# FB_Control.net
KiCad netlist of a schematic drawn in Altium Designer
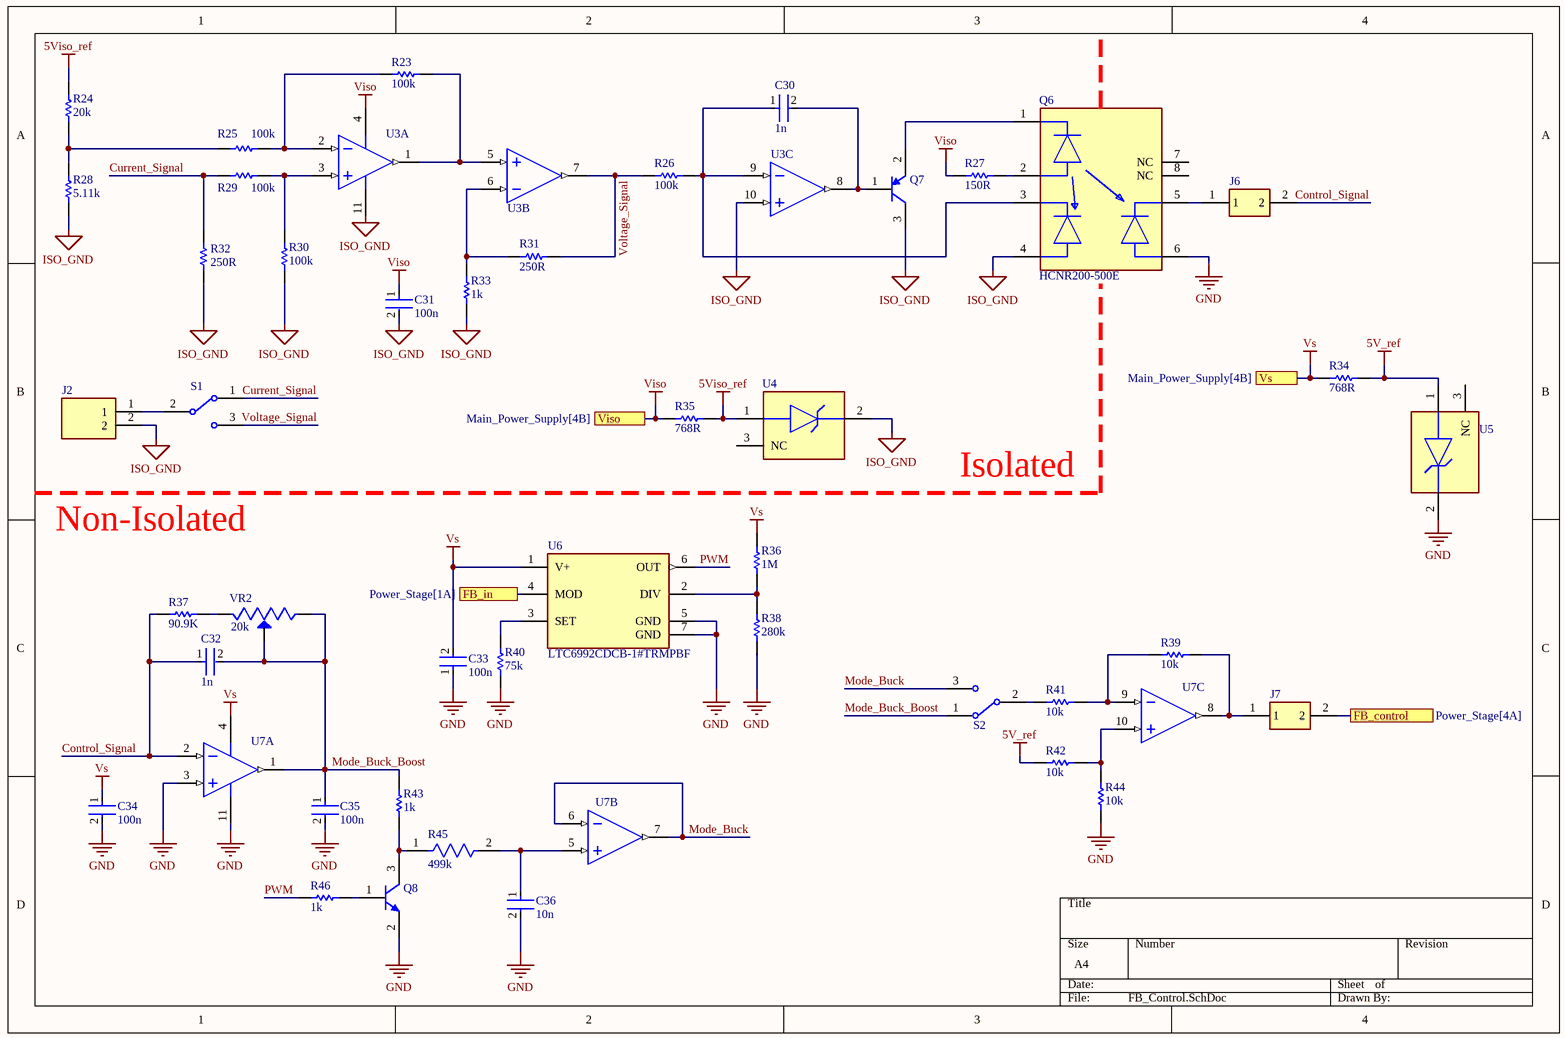
[diagram p0: FB_Control.SchDoc]

(export (version "E")
  (design (tool "Eeschema 10.0.6"))
  (components
    (comp (ref "C30")
      (value "1n")
      (footprint "FP-1206-L_3_2_0_2-W_1_6_0-IPC_C")
      (description "General Purpose Ceramic Capacitor, 1206, 1nF, 5%, NP0, 30ppm/°C, 100V")
      (fields (field (name "VOLTAGE") "100V") (field (name "TOLERANCE") "5%"))
      (libsource (lib "Altium Content Vault") (part "02cd4be3c70576c341d710602a673aa"))
    )
    (comp (ref "C31")
      (value "100n")
      (footprint "FP-0805-L_2_01_0_2-W_1_25-MFG")
      (description "General Purpose Ceramic Capacitor, 0805, 100nF, 5%, X7R, 0.15, 50V")
      (fields (field (name "TOLERANCE") "5%") (field (name "VOLTAGE") "50V"))
      (libsource (lib "Altium Content Vault") (part "02cd4be3c70576c341d710602a673aa"))
    )
    (comp (ref "C32")
      (value "1n")
      (footprint "FP-1206-L_3_2_0_2-W_1_6_0-IPC_C")
      (description "General Purpose Ceramic Capacitor, 1206, 1nF, 5%, NP0, 30ppm/°C, 100V")
      (fields (field (name "VOLTAGE") "100V") (field (name "TOLERANCE") "5%"))
      (libsource (lib "Altium Content Vault") (part "02cd4be3c70576c341d710602a673aa"))
    )
    (comp (ref "C33")
      (value "100n")
      (footprint "FP-0805-L_2_01_0_2-W_1_25-MFG")
      (description "General Purpose Ceramic Capacitor, 0805, 100nF, 5%, X7R, 0.15, 50V")
      (fields (field (name "TOLERANCE") "5%") (field (name "VOLTAGE") "50V"))
      (libsource (lib "Altium Content Vault") (part "02cd4be3c70576c341d710602a673aa"))
    )
    (comp (ref "C34")
      (value "100n")
      (footprint "FP-0805-L_2_01_0_2-W_1_25-MFG")
      (description "General Purpose Ceramic Capacitor, 0805, 100nF, 5%, X7R, 0.15, 50V")
      (fields (field (name "TOLERANCE") "5%") (field (name "VOLTAGE") "50V"))
      (libsource (lib "Altium Content Vault") (part "02cd4be3c70576c341d710602a673aa"))
    )
    (comp (ref "C35")
      (value "100n")
      (footprint "FP-0805-L_2_01_0_2-W_1_25-MFG")
      (description "General Purpose Ceramic Capacitor, 0805, 100nF, 5%, X7R, 0.15, 50V")
      (fields (field (name "TOLERANCE") "5%") (field (name "VOLTAGE") "50V"))
      (libsource (lib "Altium Content Vault") (part "02cd4be3c70576c341d710602a673aa"))
    )
    (comp (ref "C36")
      (value "10n")
      (footprint "FP-0805-L_2_01_0_2-W_1_25-IPC_B")
      (description "General Purpose Ceramic Capacitor, 0805, 10nF, 5%, X7R, 0.15, 50V")
      (fields (field (name "VOLTAGE") "50V") (field (name "TOLERANCE") "5%"))
      (libsource (lib "Altium Content Vault") (part "02cd4be3c70576c341d710602a673aa"))
    )
    (comp (ref "J2")
      (value "TB001-500-02BE")
      (footprint "Library:TB00150002BE")
      (description "Integrated Circuit")
      (fields (field (name "MOUSER PART NUMBER") "490-TB001-500-02BE"))
      (libsource (lib "Library") (part "TB001-500-02BE"))
    )
    (comp (ref "J6")
      (value "22-28-4020")
      (footprint "Library:MOLEX_22-28-4020")
      (description "Connector Header Through Hole 2 position 0.100 (2.54mm)")
      (fields (field (name "MF") "Molex"))
      (libsource (lib "Library") (part "22-28-4020"))
    )
    (comp (ref "J7")
      (value "22-28-4020")
      (footprint "Library:MOLEX_22-28-4020")
      (description "Connector Header Through Hole 2 position 0.100 (2.54mm)")
      (fields (field (name "MF") "Molex"))
      (libsource (lib "Library") (part "22-28-4020"))
    )
    (comp (ref "Q6")
      (value "HCNR200-500E")
      (footprint "FP-HCNR200-500E-MFG")
      (description "OPTOISO 5KV LINEAR PHVOLT 8DIPGW")
      (fields
        (field (name "MANUFACTURER") "Broadcom")
        (field (name "OCTOPART") "https://octopart.com/hcnr200-500e-broadcom-71127619")
      )
      (libsource (lib "Altium Content Vault") (part "ed3c43dafd640b596a0c0b735e2ad1a"))
    )
    (comp (ref "Q7")
      (value "MMBT3906TT1G")
      (footprint "ONSC-SC-75-3-463-01_V")
      (description "General Purpose Transistor, PNP Silicon, 3-Pin SC-75, Pb-Free, Tape and Reel")
      (fields (field (name "MANUFACTURER") "On Semiconductor"))
      (libsource (lib "Altium Content Vault") (part "ONSC-PNP-B1E2C3-3"))
    )
    (comp (ref "Q8")
      (value "MMBT3904LT1G")
      (footprint "ONSC-SOT-23-3-318-08_V")
      (description "General Purpose Transistor, NPN Silicon, 3-Pin SOT-23, Pb-Free, Tape and Reel")
      (fields (field (name "MANUFACTURER") "On Semiconductor"))
      (libsource (lib "Altium Content Vault") (part "ONSC-NPN-B1E2C3-3"))
    )
    (comp (ref "R23")
      (value "100k")
      (footprint "RESC1608X55X30ML15T15")
      (fields (field (name "PART NUMBER") "ERJ-3EKF1003V") (field (name "MANUFACTURER") "Panasonic"))
      (libsource (lib "Altium Content Vault") (part "RES"))
    )
    (comp (ref "R24")
      (value "20k")
      (footprint "RESC1608X55X30ML15T15")
      (fields (field (name "PART NUMBER") "ERJ-3EKF2002V") (field (name "MANUFACTURER") "Panasonic"))
      (libsource (lib "Altium Content Vault") (part "RES"))
    )
    (comp (ref "R25")
      (value "100k")
      (footprint "RESC1608X55X30ML15T15")
      (fields (field (name "PART NUMBER") "ERJ-3EKF1003V") (field (name "MANUFACTURER") "Panasonic"))
      (libsource (lib "Altium Content Vault") (part "RES"))
    )
    (comp (ref "R26")
      (value "100k")
      (footprint "RESC1608X55X30ML15T15")
      (fields (field (name "PART NUMBER") "ERJ-3EKF1003V") (field (name "MANUFACTURER") "Panasonic"))
      (libsource (lib "Altium Content Vault") (part "RES"))
    )
    (comp (ref "R27")
      (value "150R")
      (footprint "RESC1608X55X30NL15T15")
      (fields (field (name "PART NUMBER") "ERJ-3EKF1500V") (field (name "MANUFACTURER") "Panasonic"))
      (libsource (lib "Altium Content Vault") (part "RES"))
    )
    (comp (ref "R28")
      (value "5.11k")
      (footprint "RESC1608X55X30LL15T15")
      (fields (field (name "PART NUMBER") "ERJ-3EKF5111V") (field (name "MANUFACTURER") "Panasonic"))
      (libsource (lib "Altium Content Vault") (part "RES"))
    )
    (comp (ref "R29")
      (value "100k")
      (footprint "RESC1608X55X30ML15T15")
      (fields (field (name "PART NUMBER") "ERJ-3EKF1003V") (field (name "MANUFACTURER") "Panasonic"))
      (libsource (lib "Altium Content Vault") (part "RES"))
    )
    (comp (ref "R30")
      (value "100k")
      (footprint "RESC1608X55X30ML15T15")
      (fields (field (name "PART NUMBER") "ERJ-3EKF1003V") (field (name "MANUFACTURER") "Panasonic"))
      (libsource (lib "Altium Content Vault") (part "RES"))
    )
    (comp (ref "R31")
      (value "250R")
      (footprint "Library:RESC1608X55N")
      (description "Thin Film Resistors - SMD 250 ohm 0.1% 50 ppm High-Precision RT0603BRE07250RL")
      (fields
        (field (name "MANUFACTURER_PART_NUMBER") "RT0603BRE07250RL")
        (field (name "MOUSER PART NUMBER") "603-RT0603BRE07250RL")
      )
      (libsource (lib "Library") (part "RT0603BRE07250RL"))
    )
    (comp (ref "R32")
      (value "250R")
      (footprint "Library:RESC1608X55N")
      (description "Thin Film Resistors - SMD 250 ohm 0.1% 50 ppm High-Precision RT0603BRE07250RL")
      (fields
        (field (name "MANUFACTURER_PART_NUMBER") "RT0603BRE07250RL")
        (field (name "MOUSER PART NUMBER") "603-RT0603BRE07250RL")
      )
      (libsource (lib "Library") (part "RT0603BRE07250RL"))
    )
    (comp (ref "R33")
      (value "1k")
      (footprint "RESC1608X55X30LL15T15")
      (fields (field (name "PART NUMBER") "ERJ-3EKF1001V") (field (name "MANUFACTURER") "Panasonic"))
      (libsource (lib "Altium Content Vault") (part "RES"))
    )
    (comp (ref "R34")
      (value "768R")
      (footprint "RESC1608X55X30LL15T15")
      (fields (field (name "PART NUMBER") "ERJ-3EKF7680V") (field (name "MANUFACTURER") "Panasonic"))
      (libsource (lib "Altium Content Vault") (part "RES"))
    )
    (comp (ref "R35")
      (value "768R")
      (footprint "RESC1608X55X30LL15T15")
      (fields (field (name "PART NUMBER") "ERJ-3EKF7680V") (field (name "MANUFACTURER") "Panasonic"))
      (libsource (lib "Altium Content Vault") (part "RES"))
    )
    (comp (ref "R36")
      (value "1M")
      (footprint "RESC1608X55X25LL10T15")
      (description "Chip Resistor, 1 MOhm, +/- 1%, 100 mW, -55 to 155 degC, 0603 (1608 Metric), RoHS, Tape and Reel")
      (fields (field (name "TOLERANCE") "20%"))
      (libsource (lib "Altium Content Vault") (part "RES-2"))
    )
    (comp (ref "R37")
      (value "90.9K")
      (footprint "RESC1608X55X30ML15T15")
      (fields (field (name "MANUFACTURER") "Panasonic") (field (name "PART NUMBER") "ERJ-3EKF9092V"))
      (libsource (lib "Altium Content Vault") (part "RES"))
    )
    (comp (ref "R38")
      (value "280k")
      (footprint "RESC1608X55X30LL15T15")
      (fields (field (name "MANUFACTURER") "Panasonic") (field (name "PART NUMBER") "ERJ-3EKF2803V"))
      (libsource (lib "Altium Content Vault") (part "RES"))
    )
    (comp (ref "R39")
      (value "10k")
      (footprint "RESC1609X55X30LL15T15")
      (description "Chip Resistor, 10 KOhm, +/- 1%, 0.1 W, -55 to 155 degC, 0603 (1608 Metric), RoHS, Tape and Reel")
      (fields (field (name "TOLERANCE") "1%") (field (name "MANUFACTURER") "Panasonic"))
      (libsource (lib "Altium Content Vault") (part "RES-2"))
    )
    (comp (ref "R40")
      (value "75k")
      (footprint "RESC1608X55X30NL15T15")
      (fields (field (name "PART NUMBER") "ERJ-3EKF7502V") (field (name "MANUFACTURER") "Panasonic"))
      (libsource (lib "Altium Content Vault") (part "RES"))
    )
    (comp (ref "R41")
      (value "10k")
      (footprint "RESC1609X55X30LL15T15")
      (description "Chip Resistor, 10 KOhm, +/- 1%, 0.1 W, -55 to 155 degC, 0603 (1608 Metric), RoHS, Tape and Reel")
      (fields (field (name "TOLERANCE") "1%") (field (name "MANUFACTURER") "Panasonic"))
      (libsource (lib "Altium Content Vault") (part "RES-2"))
    )
    (comp (ref "R42")
      (value "10k")
      (footprint "RESC1609X55X30LL15T15")
      (description "Chip Resistor, 10 KOhm, +/- 1%, 0.1 W, -55 to 155 degC, 0603 (1608 Metric), RoHS, Tape and Reel")
      (fields (field (name "TOLERANCE") "1%") (field (name "MANUFACTURER") "Panasonic"))
      (libsource (lib "Altium Content Vault") (part "RES-2"))
    )
    (comp (ref "R43")
      (value "1k")
      (footprint "RESC1608X55X30LL15T15")
      (fields (field (name "PART NUMBER") "ERJ-3EKF1001V") (field (name "MANUFACTURER") "Panasonic"))
      (libsource (lib "Altium Content Vault") (part "RES"))
    )
    (comp (ref "R44")
      (value "10k")
      (footprint "RESC1609X55X30LL15T15")
      (description "Chip Resistor, 10 KOhm, +/- 1%, 0.1 W, -55 to 155 degC, 0603 (1608 Metric), RoHS, Tape and Reel")
      (fields (field (name "TOLERANCE") "1%") (field (name "MANUFACTURER") "Panasonic"))
      (libsource (lib "Altium Content Vault") (part "RES-2"))
    )
    (comp (ref "R45")
      (value "499k")
      (footprint "FP-ERJ3EK-IPC_B")
      (description "RES SMD 499K OHM 1% 1/10W 0603")
      (fields (field (name "TOLERANCE") "1%"))
      (libsource (lib "Altium Content Vault") (part "1029c3af85768c4190bb7ad29bc67b5"))
    )
    (comp (ref "R46")
      (value "1k")
      (footprint "RESC1608X55X30LL15T15")
      (fields (field (name "PART NUMBER") "ERJ-3EKF1001V") (field (name "MANUFACTURER") "Panasonic"))
      (libsource (lib "Altium Content Vault") (part "RES"))
    )
    (comp (ref "S1")
      (value "100SP1T1B1M2QEH")
      (footprint "Library:100SP1T1B4M2QE")
      (description "Switch")
      (fields (field (name "MOUSER PART NUMBER") "612-100-A1121"))
      (libsource (lib "Library") (part "100SP1T1B1M2QEH"))
    )
    (comp (ref "S2")
      (value "100SP1T1B1M2QEH")
      (footprint "Library:100SP1T1B4M2QE")
      (description "Switch")
      (fields (field (name "MOUSER PART NUMBER") "612-100-A1121"))
      (libsource (lib "Library") (part "100SP1T1B1M2QEH"))
    )
    (comp (ref "U3")
      (value "AD8534ARUZ-REEL")
      (footprint "Library:ADI-RU-14_L")
      (fields (field (name "GENERIC PART NUMBER") "AD8534") (field (name "MANUFACTURER") "Analog Devices"))
      (libsource (lib "Library") (part "CMP-0384-01858-1"))
    )
    (comp (ref "U4")
      (value "LM4040CYM3-5.0-TR")
      (footprint "FP-SOT23-3LD-PL-1-MFG")
      (description "LM4040CYM3-5.0-TR LM4040 Series 5 V ±0.5% Precision Micropower Shunt Voltage Reference-SOT-23-3")
      (fields (field (name "TOLERANCE") "0.5%"))
      (libsource (lib "") (part "b87c8cf627959e65149297927ce676c_1"))
    )
    (comp (ref "U5")
      (value "LM4040CYM3-5.0-TR")
      (footprint "FP-SOT23-3LD-PL-1-MFG")
      (description "LM4040CYM3-5.0-TR LM4040 Series 5 V ±0.5% Precision Micropower Shunt Voltage Reference-SOT-23-3")
      (fields (field (name "TOLERANCE") "0.5%"))
      (libsource (lib "Altium Content Vault") (part "b87c8cf627959e65149297927ce676c"))
    )
    (comp (ref "U6")
      (value "LTC6992CDCB-1#TRMPBF")
      (footprint "FP-DCB-6-05-08-1715-MFG")
      (description "IC OSC SILICON PROG 6-DFN")
      (libsource (lib "Altium Content Vault") (part "e4f96c068363ec00df2eaba9be5011b"))
    )
    (comp (ref "U7")
      (value "AD8534ARUZ-REEL")
      (footprint "Library:ADI-RU-14_L")
      (fields (field (name "GENERIC PART NUMBER") "AD8534") (field (name "MANUFACTURER") "Analog Devices"))
      (libsource (lib "Library") (part "CMP-0384-01858-1"))
    )
    (comp (ref "VR2")
      (value "20k")
      (footprint "TRIM_3296W-1-203LF")
      (description "Trimmer Resistors - Through Hole 3/8\" 20Kohms Sealed Vertical Adjust")
      (fields (field (name "MF") "{'manufacturer': u'Bourns'}") (field (name "MP") "3296W-1-203LF"))
      (libsource (lib "SnapEDA_Library") (part "3296W-1-203LF"))
    )
  )
  (nets
    (net (code "1") (name "/Control_Signal") (class "Default")
      (node (ref "C32") (pin "1") (pinfunction "1_1") (pintype "passive"))
      (node (ref "J6") (pin "2") (pinfunction "2_2") (pintype "passive"))
      (node (ref "R37") (pin "1") (pinfunction "1_1") (pintype "passive"))
      (node (ref "U7") (pin "2") (pinfunction "-IN_A_2") (pintype "input"))
    )
    (net (code "2") (name "/Current_Signal") (class "Default")
      (node (ref "R29") (pin "1") (pinfunction "1_1") (pintype "passive"))
      (node (ref "R32") (pin "2") (pinfunction "2_2") (pintype "passive"))
      (node (ref "S1") (pin "1") (pinfunction "NC_1") (pintype "passive"))
    )
    (net (code "3") (name "/FB_control") (class "Default")
      (node (ref "J7") (pin "2") (pinfunction "2_2") (pintype "passive"))
    )
    (net (code "4") (name "/FB_in") (class "Default")
      (node (ref "U6") (pin "4") (pinfunction "MOD_4") (pintype "passive"))
    )
    (net (code "5") (name "/Mode_Buck") (class "Default")
      (node (ref "S2") (pin "3") (pinfunction "NO_3") (pintype "passive"))
      (node (ref "U7") (pin "6") (pinfunction "-IN_B_6") (pintype "input"))
      (node (ref "U7") (pin "7") (pinfunction "OUT_B_7") (pintype "output"))
    )
    (net (code "6") (name "/Mode_Buck_Boost") (class "Default")
      (node (ref "C32") (pin "2") (pinfunction "2_2") (pintype "passive"))
      (node (ref "C35") (pin "1") (pinfunction "1_1") (pintype "passive"))
      (node (ref "R43") (pin "2") (pinfunction "2_2") (pintype "passive"))
      (node (ref "S2") (pin "1") (pinfunction "NC_1") (pintype "passive"))
      (node (ref "U7") (pin "1") (pinfunction "OUT_A_1") (pintype "output"))
      (node (ref "VR2") (pin "1") (pinfunction "CCW_1") (pintype "passive"))
      (node (ref "VR2") (pin "2") (pinfunction "WIPER_2") (pintype "passive"))
    )
    (net (code "7") (name "/PWM") (class "Default")
      (node (ref "R46") (pin "1") (pinfunction "1_1") (pintype "passive"))
      (node (ref "U6") (pin "6") (pinfunction "OUT_6") (pintype "output"))
    )
    (net (code "8") (name "/Voltage_Signal") (class "Default")
      (node (ref "R26") (pin "1") (pinfunction "1_1") (pintype "passive"))
      (node (ref "R31") (pin "1") (pinfunction "1_1") (pintype "passive"))
      (node (ref "S1") (pin "3") (pinfunction "NO_3") (pintype "passive"))
      (node (ref "U3") (pin "7") (pinfunction "OUT_B_7") (pintype "output"))
    )
    (net (code "9") (name "5V_ref") (class "Default")
      (node (ref "R34") (pin "2") (pinfunction "2_2") (pintype "passive"))
      (node (ref "R42") (pin "2") (pinfunction "2_2") (pintype "passive"))
      (node (ref "U5") (pin "1") (pinfunction "A_1") (pintype "passive"))
    )
    (net (code "10") (name "5Viso_ref") (class "Default")
      (node (ref "R24") (pin "2") (pinfunction "2_2") (pintype "passive"))
      (node (ref "R35") (pin "2") (pinfunction "2_2") (pintype "passive"))
      (node (ref "U4") (pin "1") (pinfunction "A_1") (pintype "passive"))
    )
    (net (code "11") (name "GND") (class "Default")
      (node (ref "C33") (pin "1") (pinfunction "1_1") (pintype "passive"))
      (node (ref "C34") (pin "2") (pinfunction "2_2") (pintype "passive"))
      (node (ref "C35") (pin "2") (pinfunction "2_2") (pintype "passive"))
      (node (ref "C36") (pin "2") (pinfunction "2_2") (pintype "passive"))
      (node (ref "Q6") (pin "6") (pinfunction "PD2_CATHODE_6") (pintype "passive"))
      (node (ref "Q8") (pin "2") (pinfunction "E_2") (pintype "passive"))
      (node (ref "R38") (pin "1") (pinfunction "1_1") (pintype "passive"))
      (node (ref "R40") (pin "1") (pinfunction "1_1") (pintype "passive"))
      (node (ref "R44") (pin "2") (pinfunction "2_2") (pintype "passive"))
      (node (ref "U5") (pin "2") (pinfunction "C_2") (pintype "passive"))
      (node (ref "U6") (pin "5") (pinfunction "GND_5") (pintype "power_in"))
      (node (ref "U6") (pin "7") (pinfunction "GND_7") (pintype "power_in"))
      (node (ref "U7") (pin "11") (pinfunction "V-_11") (pintype "power_in"))
      (node (ref "U7") (pin "3") (pinfunction "+IN_A_3") (pintype "input"))
    )
    (net (code "12") (name "ISO_GND") (class "Default")
      (node (ref "C31") (pin "2") (pinfunction "2_2") (pintype "passive"))
      (node (ref "J2") (pin "2") (pinfunction "2_2") (pintype "passive"))
      (node (ref "Q6") (pin "4") (pinfunction "PD1_ANODE_4") (pintype "passive"))
      (node (ref "Q7") (pin "3") (pinfunction "C_3") (pintype "passive"))
      (node (ref "R28") (pin "1") (pinfunction "1_1") (pintype "passive"))
      (node (ref "R30") (pin "1") (pinfunction "1_1") (pintype "passive"))
      (node (ref "R32") (pin "1") (pinfunction "1_1") (pintype "passive"))
      (node (ref "R33") (pin "1") (pinfunction "1_1") (pintype "passive"))
      (node (ref "U3") (pin "10") (pinfunction "+IN_C_10") (pintype "input"))
      (node (ref "U3") (pin "11") (pinfunction "V-_11") (pintype "power_in"))
      (node (ref "U4") (pin "2") (pinfunction "C_2") (pintype "passive"))
    )
    (net (code "13") (name "Net-(Q6-LED_ANODE)") (class "Default")
      (node (ref "Q6") (pin "2") (pinfunction "LED_ANODE_2") (pintype "passive"))
      (node (ref "R27") (pin "2") (pinfunction "2_2") (pintype "passive"))
    )
    (net (code "14") (name "Net-(Q6-LED_CATHODE)") (class "Default")
      (node (ref "Q6") (pin "1") (pinfunction "LED_CATHODE_1") (pintype "passive"))
      (node (ref "Q7") (pin "2") (pinfunction "E_2") (pintype "passive"))
    )
    (net (code "15") (name "Net-(Q6-PD1_CATHODE)") (class "Default")
      (node (ref "C30") (pin "1") (pinfunction "1_1") (pintype "passive"))
      (node (ref "Q6") (pin "3") (pinfunction "PD1_CATHODE_3") (pintype "passive"))
      (node (ref "R26") (pin "2") (pinfunction "2_2") (pintype "passive"))
      (node (ref "U3") (pin "9") (pinfunction "-IN_C_9") (pintype "input"))
    )
    (net (code "16") (name "Net-(Q6-PD2_ANODE)") (class "Default")
      (node (ref "J6") (pin "1") (pinfunction "1_1") (pintype "passive"))
      (node (ref "Q6") (pin "5") (pinfunction "PD2_ANODE_5") (pintype "passive"))
    )
    (net (code "17") (name "Net-(Q7-B)") (class "Default")
      (node (ref "C30") (pin "2") (pinfunction "2_2") (pintype "passive"))
      (node (ref "Q7") (pin "1") (pinfunction "B_1") (pintype "passive"))
      (node (ref "U3") (pin "8") (pinfunction "OUT_C_8") (pintype "output"))
    )
    (net (code "18") (name "Net-(Q8-B)") (class "Default")
      (node (ref "Q8") (pin "1") (pinfunction "B_1") (pintype "passive"))
      (node (ref "R46") (pin "2") (pinfunction "2_2") (pintype "passive"))
    )
    (net (code "19") (name "Net-(Q8-C)") (class "Default")
      (node (ref "Q8") (pin "3") (pinfunction "C_3") (pintype "passive"))
      (node (ref "R43") (pin "1") (pinfunction "1_1") (pintype "passive"))
      (node (ref "R45") (pin "1") (pinfunction "1_1") (pintype "passive"))
    )
    (net (code "20") (name "Net-(R24-Pad1)") (class "Default")
      (node (ref "R24") (pin "1") (pinfunction "1_1") (pintype "passive"))
      (node (ref "R25") (pin "1") (pinfunction "1_1") (pintype "passive"))
      (node (ref "R28") (pin "2") (pinfunction "2_2") (pintype "passive"))
    )
    (net (code "21") (name "Net-(S1-COM)") (class "Default")
      (node (ref "J2") (pin "1") (pinfunction "1_1") (pintype "passive"))
      (node (ref "S1") (pin "2") (pinfunction "COM_2") (pintype "passive"))
    )
    (net (code "22") (name "Net-(S2-COM)") (class "Default")
      (node (ref "R41") (pin "2") (pinfunction "2_2") (pintype "passive"))
      (node (ref "S2") (pin "2") (pinfunction "COM_2") (pintype "passive"))
    )
    (net (code "23") (name "Net-(U3A-+IN_A)") (class "Default")
      (node (ref "R29") (pin "2") (pinfunction "2_2") (pintype "passive"))
      (node (ref "R30") (pin "2") (pinfunction "2_2") (pintype "passive"))
      (node (ref "U3") (pin "3") (pinfunction "+IN_A_3") (pintype "input"))
    )
    (net (code "24") (name "Net-(U3A--IN_A)") (class "Default")
      (node (ref "R23") (pin "1") (pinfunction "1_1") (pintype "passive"))
      (node (ref "R25") (pin "2") (pinfunction "2_2") (pintype "passive"))
      (node (ref "U3") (pin "2") (pinfunction "-IN_A_2") (pintype "input"))
    )
    (net (code "25") (name "Net-(U3A-OUT_A)") (class "Default")
      (node (ref "R23") (pin "2") (pinfunction "2_2") (pintype "passive"))
      (node (ref "U3") (pin "1") (pinfunction "OUT_A_1") (pintype "output"))
      (node (ref "U3") (pin "5") (pinfunction "+IN_B_5") (pintype "input"))
    )
    (net (code "26") (name "Net-(U3B--IN_B)") (class "Default")
      (node (ref "R31") (pin "2") (pinfunction "2_2") (pintype "passive"))
      (node (ref "R33") (pin "2") (pinfunction "2_2") (pintype "passive"))
      (node (ref "U3") (pin "6") (pinfunction "-IN_B_6") (pintype "input"))
    )
    (net (code "27") (name "Net-(U6-DIV)") (class "Default")
      (node (ref "R36") (pin "1") (pinfunction "1_1") (pintype "passive"))
      (node (ref "R38") (pin "2") (pinfunction "2_2") (pintype "passive"))
      (node (ref "U6") (pin "2") (pinfunction "DIV_2") (pintype "passive"))
    )
    (net (code "28") (name "Net-(U6-SET)") (class "Default")
      (node (ref "R40") (pin "2") (pinfunction "2_2") (pintype "passive"))
      (node (ref "U6") (pin "3") (pinfunction "SET_3") (pintype "passive"))
    )
    (net (code "29") (name "Net-(U7B-+IN_B)") (class "Default")
      (node (ref "C36") (pin "1") (pinfunction "1_1") (pintype "passive"))
      (node (ref "R45") (pin "2") (pinfunction "2_2") (pintype "passive"))
      (node (ref "U7") (pin "5") (pinfunction "+IN_B_5") (pintype "input"))
    )
    (net (code "30") (name "Net-(U7C-+IN_C)") (class "Default")
      (node (ref "R42") (pin "1") (pinfunction "1_1") (pintype "passive"))
      (node (ref "R44") (pin "1") (pinfunction "1_1") (pintype "passive"))
      (node (ref "U7") (pin "10") (pinfunction "+IN_C_10") (pintype "input"))
    )
    (net (code "31") (name "Net-(U7C--IN_C)") (class "Default")
      (node (ref "R39") (pin "2") (pinfunction "2_2") (pintype "passive"))
      (node (ref "R41") (pin "1") (pinfunction "1_1") (pintype "passive"))
      (node (ref "U7") (pin "9") (pinfunction "-IN_C_9") (pintype "input"))
    )
    (net (code "32") (name "Net-(U7C-OUT_C)") (class "Default")
      (node (ref "J7") (pin "1") (pinfunction "1_1") (pintype "passive"))
      (node (ref "R39") (pin "1") (pinfunction "1_1") (pintype "passive"))
      (node (ref "U7") (pin "8") (pinfunction "OUT_C_8") (pintype "output"))
    )
    (net (code "33") (name "Net-(VR2-CW)") (class "Default")
      (node (ref "R37") (pin "2") (pinfunction "2_2") (pintype "passive"))
      (node (ref "VR2") (pin "3") (pinfunction "CW_3") (pintype "passive"))
    )
    (net (code "34") (name "Viso") (class "Default")
      (node (ref "C31") (pin "1") (pinfunction "1_1") (pintype "passive"))
      (node (ref "R27") (pin "1") (pinfunction "1_1") (pintype "passive"))
      (node (ref "R35") (pin "1") (pinfunction "1_1") (pintype "passive"))
      (node (ref "U3") (pin "4") (pinfunction "V+_4") (pintype "power_in"))
    )
    (net (code "35") (name "Vs") (class "Default")
      (node (ref "C33") (pin "2") (pinfunction "2_2") (pintype "passive"))
      (node (ref "C34") (pin "1") (pinfunction "1_1") (pintype "passive"))
      (node (ref "R34") (pin "1") (pinfunction "1_1") (pintype "passive"))
      (node (ref "R36") (pin "2") (pinfunction "2_2") (pintype "passive"))
      (node (ref "U6") (pin "1") (pinfunction "V+_1") (pintype "power_in"))
      (node (ref "U7") (pin "4") (pinfunction "V+_4") (pintype "power_in"))
    )
    (net (code "36") (name "unconnected-(Q6-NC-Pad7)") (class "Default")
      (node (ref "Q6") (pin "7") (pinfunction "NC_7") (pintype "passive"))
    )
    (net (code "37") (name "unconnected-(Q6-NC-Pad8)") (class "Default")
      (node (ref "Q6") (pin "8") (pinfunction "NC_8") (pintype "passive"))
    )
    (net (code "38") (name "unconnected-(U4-NC-Pad3)") (class "Default")
      (node (ref "U4") (pin "3") (pinfunction "NC_3") (pintype "passive"))
    )
    (net (code "39") (name "unconnected-(U5-NC-Pad3)") (class "Default")
      (node (ref "U5") (pin "3") (pinfunction "NC_3") (pintype "passive"))
    )
  )
)
